# DVR8421.net
KiCad netlist of a schematic drawn in Altium Designer
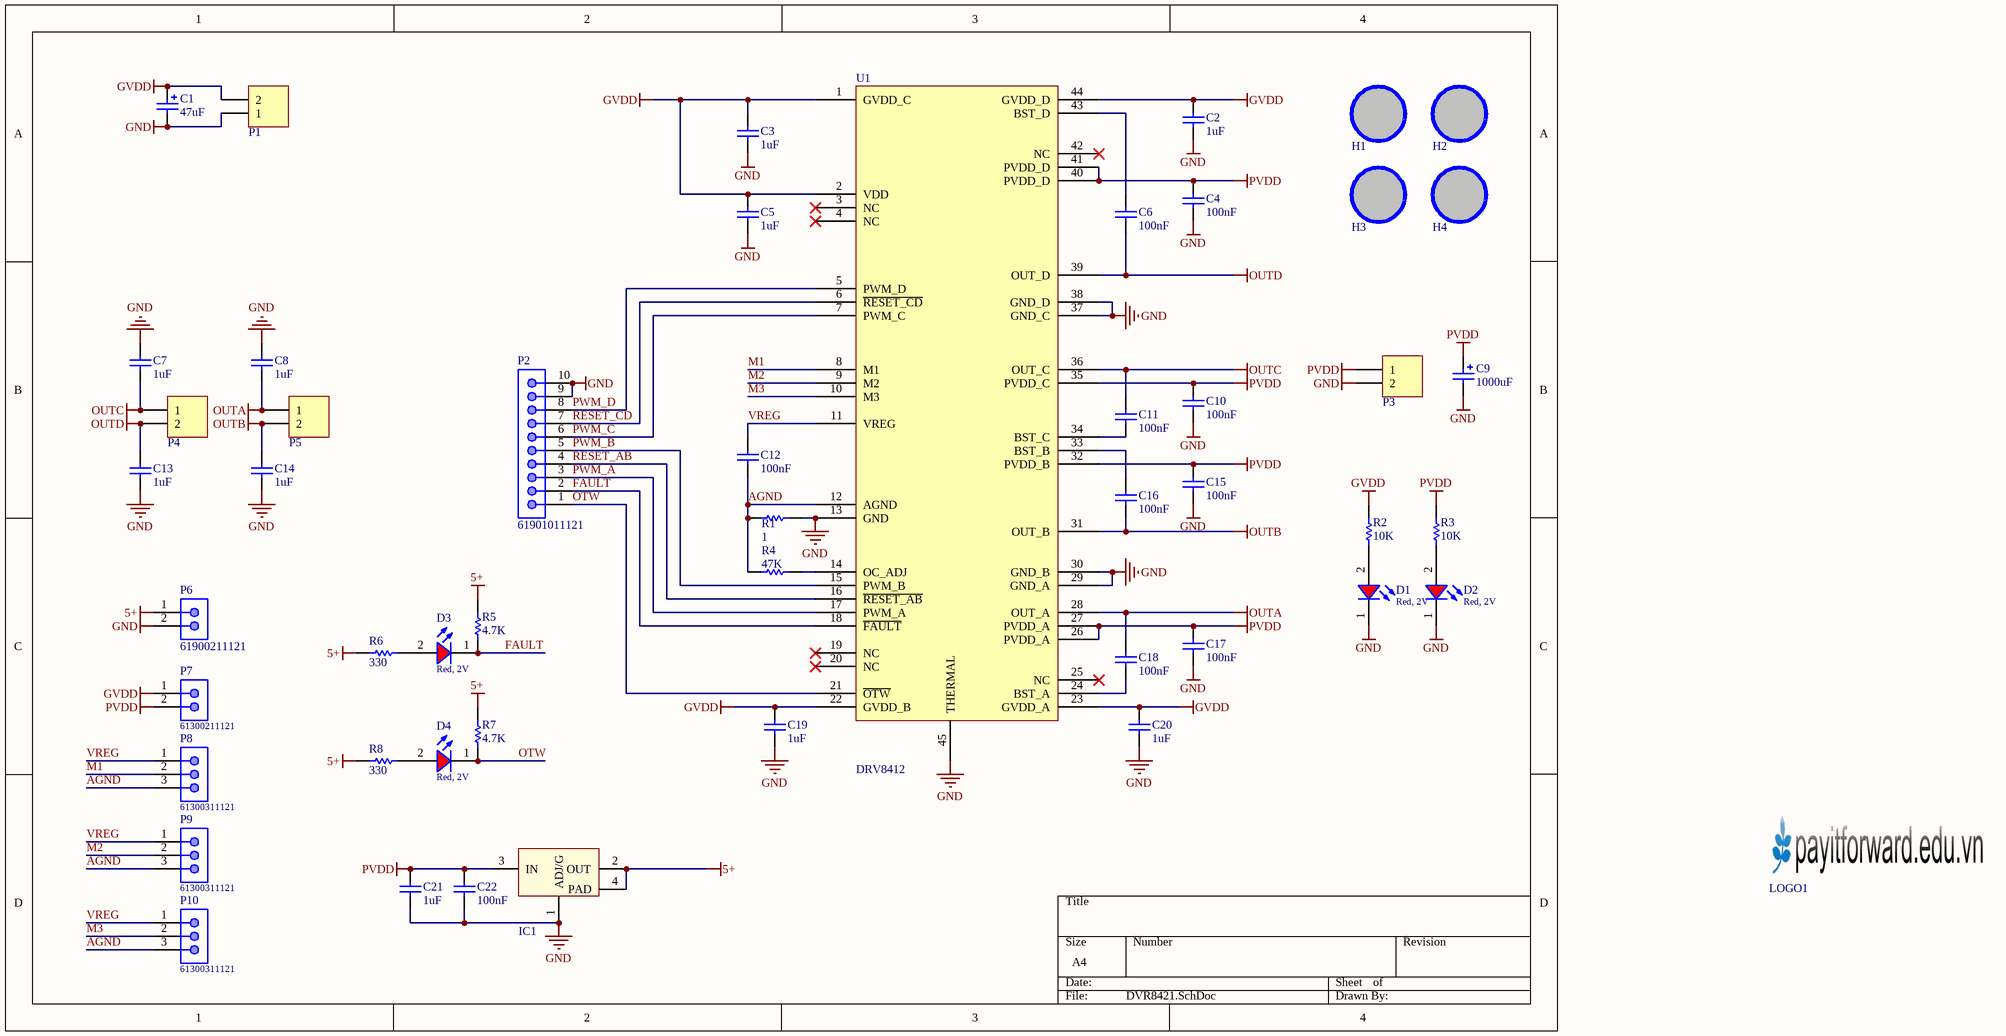
[diagram p0: DVR8421.SchDoc]

(export (version "E")
  (design (tool "Eeschema 10.0.6"))
  (components
    (comp (ref "C1")
      (value "47uF")
      (footprint "CAP ALU SIZE D")
      (description "Polarized Capacitor (Radial)")
      (fields (field (name "Comment") "Cap Pol SMD"))
      (libsource (lib "PIF_Library") (part "Cap Pol SMD"))
    )
    (comp (ref "C2")
      (value "1uF")
      (footprint "CAP-SM-0603")
      (description "Capacitor")
      (fields (field (name "Comment") "Cap Non-Pol SMD"))
      (libsource (lib "PIF_Library") (part "Cap Non-Pol SMD"))
    )
    (comp (ref "C3")
      (value "1uF")
      (footprint "CAP-SM-0603")
      (description "Capacitor")
      (fields (field (name "Comment") "Cap Non-Pol SMD"))
      (libsource (lib "PIF_Library") (part "Cap Non-Pol SMD"))
    )
    (comp (ref "C4")
      (value "100nF")
      (footprint "CAP-SM-0603")
      (description "Capacitor")
      (fields (field (name "Comment") "Cap Non-Pol SMD"))
      (libsource (lib "PIF_Library") (part "Cap Non-Pol SMD"))
    )
    (comp (ref "C5")
      (value "1uF")
      (footprint "CAP-SM-0603")
      (description "Capacitor")
      (fields (field (name "Comment") "Cap Non-Pol SMD"))
      (libsource (lib "PIF_Library") (part "Cap Non-Pol SMD"))
    )
    (comp (ref "C6")
      (value "100nF")
      (footprint "CAP-SM-0603")
      (description "Capacitor")
      (fields (field (name "Comment") "Cap Non-Pol SMD"))
      (libsource (lib "PIF_Library") (part "Cap Non-Pol SMD"))
    )
    (comp (ref "C7")
      (value "1uF")
      (footprint "CAP-SM-0805")
      (description "Capacitor")
      (fields (field (name "Comment") "Cap Non-Pol SMD"))
      (libsource (lib "PIF_Library") (part "Cap Non-Pol SMD"))
    )
    (comp (ref "C8")
      (value "1uF")
      (footprint "CAP-SM-0805")
      (description "Capacitor")
      (fields (field (name "Comment") "Cap Non-Pol SMD"))
      (libsource (lib "PIF_Library") (part "Cap Non-Pol SMD"))
    )
    (comp (ref "C9")
      (value "1000uF")
      (footprint "CP2/5")
      (description "Polarized Capacitor (Radial)")
      (fields (field (name "Comment") "Cap Pol"))
      (libsource (lib "PIF_Library") (part "Cap Pol"))
    )
    (comp (ref "C10")
      (value "100nF")
      (footprint "CAP-SM-0603")
      (description "Capacitor")
      (fields (field (name "Comment") "Cap Non-Pol SMD"))
      (libsource (lib "PIF_Library") (part "Cap Non-Pol SMD"))
    )
    (comp (ref "C11")
      (value "100nF")
      (footprint "CAP-SM-0603")
      (description "Capacitor")
      (fields (field (name "Comment") "Cap Non-Pol SMD"))
      (libsource (lib "PIF_Library") (part "Cap Non-Pol SMD"))
    )
    (comp (ref "C12")
      (value "100nF")
      (footprint "CAP-SM-0603")
      (description "Capacitor")
      (fields (field (name "Comment") "Cap Non-Pol SMD"))
      (libsource (lib "PIF_Library") (part "Cap Non-Pol SMD"))
    )
    (comp (ref "C13")
      (value "1uF")
      (footprint "CAP-SM-0805")
      (description "Capacitor")
      (fields (field (name "Comment") "Cap Non-Pol SMD"))
      (libsource (lib "PIF_Library") (part "Cap Non-Pol SMD"))
    )
    (comp (ref "C14")
      (value "1uF")
      (footprint "CAP-SM-0805")
      (description "Capacitor")
      (fields (field (name "Comment") "Cap Non-Pol SMD"))
      (libsource (lib "PIF_Library") (part "Cap Non-Pol SMD"))
    )
    (comp (ref "C15")
      (value "100nF")
      (footprint "CAP-SM-0603")
      (description "Capacitor")
      (fields (field (name "Comment") "Cap Non-Pol SMD"))
      (libsource (lib "PIF_Library") (part "Cap Non-Pol SMD"))
    )
    (comp (ref "C16")
      (value "100nF")
      (footprint "CAP-SM-0603")
      (description "Capacitor")
      (fields (field (name "Comment") "Cap Non-Pol SMD"))
      (libsource (lib "PIF_Library") (part "Cap Non-Pol SMD"))
    )
    (comp (ref "C17")
      (value "100nF")
      (footprint "CAP-SM-0603")
      (description "Capacitor")
      (fields (field (name "Comment") "Cap Non-Pol SMD"))
      (libsource (lib "PIF_Library") (part "Cap Non-Pol SMD"))
    )
    (comp (ref "C18")
      (value "100nF")
      (footprint "CAP-SM-0603")
      (description "Capacitor")
      (fields (field (name "Comment") "Cap Non-Pol SMD"))
      (libsource (lib "PIF_Library") (part "Cap Non-Pol SMD"))
    )
    (comp (ref "C19")
      (value "1uF")
      (footprint "CAP-SM-0603")
      (description "Capacitor")
      (fields (field (name "Comment") "Cap Non-Pol SMD"))
      (libsource (lib "PIF_Library") (part "Cap Non-Pol SMD"))
    )
    (comp (ref "C20")
      (value "1uF")
      (footprint "CAP-SM-0603")
      (description "Capacitor")
      (fields (field (name "Comment") "Cap Non-Pol SMD"))
      (libsource (lib "PIF_Library") (part "Cap Non-Pol SMD"))
    )
    (comp (ref "C21")
      (value "1uF")
      (footprint "CAP-SM-0603")
      (description "Capacitor")
      (fields (field (name "Comment") "Cap Non-Pol SMD"))
      (libsource (lib "PIF_Library") (part "Cap Non-Pol SMD"))
    )
    (comp (ref "C22")
      (value "100nF")
      (footprint "CAP-SM-0603")
      (description "Capacitor")
      (fields (field (name "Comment") "Cap Non-Pol SMD"))
      (libsource (lib "PIF_Library") (part "Cap Non-Pol SMD"))
    )
    (comp (ref "D1")
      (value "Red, 2V")
      (footprint "WL-SMCW_0603_H=0.7mm")
      (description "WL-SMCW SMT Mono-color Chip LED Waterclear, size 0603, Red, 2V, 140deg")
      (fields (field (name "PART NUMBER") "150060RS75000") (field (name "PUBLISHER") "Wurth Elektronik"))
      (libsource (lib "Altium_WL-SMCW (rev20a)") (part "150060RS75000"))
    )
    (comp (ref "D2")
      (value "Red, 2V")
      (footprint "WL-SMCW_0603_H=0.7mm")
      (description "WL-SMCW SMT Mono-color Chip LED Waterclear, size 0603, Red, 2V, 140deg")
      (fields (field (name "PART NUMBER") "150060RS75000") (field (name "PUBLISHER") "Wurth Elektronik"))
      (libsource (lib "Altium_WL-SMCW (rev20a)") (part "150060RS75000"))
    )
    (comp (ref "D3")
      (value "Red, 2V")
      (footprint "WL-SMCW_0603_H=0.7mm")
      (description "WL-SMCW SMT Mono-color Chip LED Waterclear, size 0603, Red, 2V, 140deg")
      (fields (field (name "PART NUMBER") "150060RS75000") (field (name "PUBLISHER") "Wurth Elektronik"))
      (libsource (lib "Altium_WL-SMCW (rev20a)") (part "150060RS75000"))
    )
    (comp (ref "D4")
      (value "Red, 2V")
      (footprint "WL-SMCW_0603_H=0.7mm")
      (description "WL-SMCW SMT Mono-color Chip LED Waterclear, size 0603, Red, 2V, 140deg")
      (fields (field (name "PART NUMBER") "150060RS75000") (field (name "PUBLISHER") "Wurth Elektronik"))
      (libsource (lib "Altium_WL-SMCW (rev20a)") (part "150060RS75000"))
    )
    (comp (ref "H1")
      (value "Hole")
      (footprint "LO KHOAN 3MM")
      (description "Hole 3mm")
      (libsource (lib "PIF_Library") (part "Hole"))
    )
    (comp (ref "H2")
      (value "Hole")
      (footprint "LO KHOAN 3MM")
      (description "Hole 3mm")
      (libsource (lib "PIF_Library") (part "Hole"))
    )
    (comp (ref "H3")
      (value "Hole")
      (footprint "LO KHOAN 3MM")
      (description "Hole 3mm")
      (libsource (lib "PIF_Library") (part "Hole"))
    )
    (comp (ref "H4")
      (value "Hole")
      (footprint "LO KHOAN 3MM")
      (description "Hole 3mm")
      (libsource (lib "PIF_Library") (part "Hole"))
    )
    (comp (ref "IC1")
      (value "LM1117")
      (footprint "SOT223-4N")
      (description "Available in 1.8V, 2.5V, 2.85V, 3.3V, 5V, and  Adjustable Versions")
      (libsource (lib "PIF_Library") (part "LM1117"))
    )
    (comp (ref "LOGO1")
      (value "LOGO PIF")
      (footprint "PIF LOGO SMALL TOP")
      (libsource (lib "PIF_Library") (part "LOGO PIF"))
    )
    (comp (ref "P1")
      (value "Domino 2")
      (footprint "DOMINO 2- 5mm")
      (description "Domino, 2-Pin")
      (fields (field (name "PUBLISHER") "Altium Limited"))
      (libsource (lib "") (part "Domino 2_1"))
    )
    (comp (ref "P2")
      (value "61901011121")
      (footprint "61901011121")
      (description "WR-WTB THT Male Vertical Locking Header, pitch 2.54mm, 10p")
      (fields (field (name "PUBLISHER") "Wurth Elektronik"))
      (libsource (lib "653008114822_Altium_WR-WTB_rev20a") (part "61901011121"))
    )
    (comp (ref "P3")
      (value "Domino 2")
      (footprint "DOMINO 2- 5mm")
      (description "Domino, 2-Pin")
      (fields (field (name "PUBLISHER") "Altium Limited"))
      (libsource (lib "PIF_Library") (part "Domino 2"))
    )
    (comp (ref "P4")
      (value "Domino 2")
      (footprint "DOMINO 2- 5mm")
      (description "Domino, 2-Pin")
      (fields (field (name "PUBLISHER") "Altium Limited"))
      (libsource (lib "PIF_Library") (part "Domino 2"))
    )
    (comp (ref "P5")
      (value "Domino 2")
      (footprint "DOMINO 2- 5mm")
      (description "Domino, 2-Pin")
      (fields (field (name "PUBLISHER") "Altium Limited"))
      (libsource (lib "PIF_Library") (part "Domino 2"))
    )
    (comp (ref "P6")
      (value "61900211121")
      (footprint "61900211121")
      (description "WR-WTB THT Male Vertical Locking Header, pitch 2.54mm, 2p")
      (fields (field (name "PUBLISHER") "Wurth Elektronik"))
      (libsource (lib "653008114822_Altium_WR-WTB_rev20a") (part "61900211121"))
    )
    (comp (ref "P7")
      (value "61300211121")
      (footprint "61300211121")
      (description "WR-PHD Pin Header, THT, pitch 2.54mm, Single Row, Vertical, 2p")
      (fields (field (name "MANUFACTURER") "Wurth Elektronik"))
      (libsource (lib "Altium_WR-PHD (rev20a)") (part "61300211121"))
    )
    (comp (ref "P8")
      (value "61300311121")
      (footprint "61300311121")
      (description "WR-PHD Pin Header, THT, pitch 2.54mm, Single Row, Vertical, 3p")
      (fields (field (name "MANUFACTURER") "Wurth Elektronik"))
      (libsource (lib "Altium_WR-PHD (rev20a)") (part "61300311121"))
    )
    (comp (ref "P9")
      (value "61300311121")
      (footprint "61300311121")
      (description "WR-PHD Pin Header, THT, pitch 2.54mm, Single Row, Vertical, 3p")
      (fields (field (name "MANUFACTURER") "Wurth Elektronik"))
      (libsource (lib "Altium_WR-PHD (rev20a)") (part "61300311121"))
    )
    (comp (ref "P10")
      (value "61300311121")
      (footprint "61300311121")
      (description "WR-PHD Pin Header, THT, pitch 2.54mm, Single Row, Vertical, 3p")
      (fields (field (name "MANUFACTURER") "Wurth Elektronik"))
      (libsource (lib "Altium_WR-PHD (rev20a)") (part "61300311121"))
    )
    (comp (ref "R1")
      (value "1")
      (footprint "RES-SM-0603")
      (description "Resistor")
      (fields (field (name "Comment") "RESISTOR SMD"))
      (libsource (lib "PIF_Library") (part "RESISTOR SMD"))
    )
    (comp (ref "R2")
      (value "10K")
      (footprint "RES-SM-0603")
      (description "Resistor")
      (fields (field (name "Comment") "RESISTOR SMD"))
      (libsource (lib "PIF_Library") (part "RESISTOR SMD"))
    )
    (comp (ref "R3")
      (value "10K")
      (footprint "RES-SM-0603")
      (description "Resistor")
      (fields (field (name "Comment") "RESISTOR SMD"))
      (libsource (lib "PIF_Library") (part "RESISTOR SMD"))
    )
    (comp (ref "R4")
      (value "47K")
      (footprint "RES-SM-0603")
      (description "Resistor")
      (fields (field (name "Comment") "RESISTOR SMD"))
      (libsource (lib "PIF_Library") (part "RESISTOR SMD"))
    )
    (comp (ref "R5")
      (value "4.7K")
      (footprint "RES-SM-0603")
      (description "Resistor")
      (fields (field (name "Comment") "RESISTOR SMD"))
      (libsource (lib "PIF_Library") (part "RESISTOR SMD"))
    )
    (comp (ref "R6")
      (value "330")
      (footprint "RES-SM-0603")
      (description "Resistor")
      (fields (field (name "Comment") "RESISTOR SMD"))
      (libsource (lib "PIF_Library") (part "RESISTOR SMD"))
    )
    (comp (ref "R7")
      (value "4.7K")
      (footprint "RES-SM-0603")
      (description "Resistor")
      (fields (field (name "Comment") "RESISTOR SMD"))
      (libsource (lib "PIF_Library") (part "RESISTOR SMD"))
    )
    (comp (ref "R8")
      (value "330")
      (footprint "RES-SM-0603")
      (description "Resistor")
      (fields (field (name "Comment") "RESISTOR SMD"))
      (libsource (lib "PIF_Library") (part "RESISTOR SMD"))
    )
    (comp (ref "U1")
      (value "DRV8412")
      (footprint "TSOP64P810X150_HS-45N")
      (fields (field (name "MANUFACTURER") "Texas Instruments"))
      (libsource (lib "MiclsLib") (part "DRV8412"))
    )
  )
  (nets
    (net (code "1") (name "/AGND") (class "Default")
      (node (ref "C12") (pin "1") (pinfunction "1_1") (pintype "passive"))
      (node (ref "P10") (pin "3") (pinfunction "3_3") (pintype "passive"))
      (node (ref "P8") (pin "3") (pinfunction "3_3") (pintype "passive"))
      (node (ref "P9") (pin "3") (pinfunction "3_3") (pintype "passive"))
      (node (ref "R1") (pin "1") (pinfunction "1_1") (pintype "passive"))
      (node (ref "R4") (pin "1") (pinfunction "1_1") (pintype "passive"))
      (node (ref "U1") (pin "12") (pinfunction "AGND_12") (pintype "passive"))
    )
    (net (code "2") (name "/FAULT") (class "Default")
      (node (ref "D3") (pin "1") (pinfunction "K_1") (pintype "passive"))
      (node (ref "P2") (pin "2") (pinfunction "2_2") (pintype "passive"))
      (node (ref "R5") (pin "1") (pinfunction "1_1") (pintype "passive"))
      (node (ref "U1") (pin "18") (pinfunction "~{FAULT}_18") (pintype "passive"))
    )
    (net (code "3") (name "/M1") (class "Default")
      (node (ref "P8") (pin "2") (pinfunction "2_2") (pintype "passive"))
      (node (ref "U1") (pin "8") (pinfunction "M1_8") (pintype "passive"))
    )
    (net (code "4") (name "/M2") (class "Default")
      (node (ref "P9") (pin "2") (pinfunction "2_2") (pintype "passive"))
      (node (ref "U1") (pin "9") (pinfunction "M2_9") (pintype "passive"))
    )
    (net (code "5") (name "/M3") (class "Default")
      (node (ref "P10") (pin "2") (pinfunction "2_2") (pintype "passive"))
      (node (ref "U1") (pin "10") (pinfunction "M3_10") (pintype "passive"))
    )
    (net (code "6") (name "/OTW") (class "Default")
      (node (ref "D4") (pin "1") (pinfunction "K_1") (pintype "passive"))
      (node (ref "P2") (pin "1") (pinfunction "1_1") (pintype "passive"))
      (node (ref "R7") (pin "1") (pinfunction "1_1") (pintype "passive"))
      (node (ref "U1") (pin "21") (pinfunction "~{OTW}_21") (pintype "passive"))
    )
    (net (code "7") (name "/PWM_A") (class "Default")
      (node (ref "P2") (pin "3") (pinfunction "3_3") (pintype "passive"))
      (node (ref "U1") (pin "17") (pinfunction "PWM_A_17") (pintype "passive"))
    )
    (net (code "8") (name "/PWM_B") (class "Default")
      (node (ref "P2") (pin "5") (pinfunction "5_5") (pintype "passive"))
      (node (ref "U1") (pin "15") (pinfunction "PWM_B_15") (pintype "passive"))
    )
    (net (code "9") (name "/PWM_C") (class "Default")
      (node (ref "P2") (pin "6") (pinfunction "6_6") (pintype "passive"))
      (node (ref "U1") (pin "7") (pinfunction "PWM_C_7") (pintype "passive"))
    )
    (net (code "10") (name "/PWM_D") (class "Default")
      (node (ref "P2") (pin "8") (pinfunction "8_8") (pintype "passive"))
      (node (ref "U1") (pin "5") (pinfunction "PWM_D_5") (pintype "passive"))
    )
    (net (code "11") (name "/RESET_AB") (class "Default")
      (node (ref "P2") (pin "4") (pinfunction "4_4") (pintype "passive"))
      (node (ref "U1") (pin "16") (pinfunction "~{RESET_AB}_16") (pintype "passive"))
    )
    (net (code "12") (name "/RESET_CD") (class "Default")
      (node (ref "P2") (pin "7") (pinfunction "7_7") (pintype "passive"))
      (node (ref "U1") (pin "6") (pinfunction "~{RESET_CD}_6") (pintype "passive"))
    )
    (net (code "13") (name "/VREG") (class "Default")
      (node (ref "C12") (pin "2") (pinfunction "2_2") (pintype "passive"))
      (node (ref "P10") (pin "1") (pinfunction "1_1") (pintype "passive"))
      (node (ref "P8") (pin "1") (pinfunction "1_1") (pintype "passive"))
      (node (ref "P9") (pin "1") (pinfunction "1_1") (pintype "passive"))
      (node (ref "U1") (pin "11") (pinfunction "VREG_11") (pintype "passive"))
    )
    (net (code "14") (name "5+") (class "Default")
      (node (ref "IC1") (pin "2") (pinfunction "OUT_2") (pintype "passive"))
      (node (ref "IC1") (pin "4") (pinfunction "PAD_4") (pintype "passive"))
      (node (ref "P6") (pin "1") (pinfunction "1_1") (pintype "passive"))
      (node (ref "R5") (pin "2") (pinfunction "2_2") (pintype "passive"))
      (node (ref "R6") (pin "2") (pinfunction "2_2") (pintype "passive"))
      (node (ref "R7") (pin "2") (pinfunction "2_2") (pintype "passive"))
      (node (ref "R8") (pin "2") (pinfunction "2_2") (pintype "passive"))
    )
    (net (code "15") (name "GND") (class "Default")
      (node (ref "C1") (pin "2") (pinfunction "2_2") (pintype "passive"))
      (node (ref "C10") (pin "1") (pinfunction "1_1") (pintype "passive"))
      (node (ref "C13") (pin "1") (pinfunction "1_1") (pintype "passive"))
      (node (ref "C14") (pin "1") (pinfunction "1_1") (pintype "passive"))
      (node (ref "C15") (pin "1") (pinfunction "1_1") (pintype "passive"))
      (node (ref "C17") (pin "1") (pinfunction "1_1") (pintype "passive"))
      (node (ref "C19") (pin "1") (pinfunction "1_1") (pintype "passive"))
      (node (ref "C2") (pin "1") (pinfunction "1_1") (pintype "passive"))
      (node (ref "C20") (pin "1") (pinfunction "1_1") (pintype "passive"))
      (node (ref "C21") (pin "1") (pinfunction "1_1") (pintype "passive"))
      (node (ref "C22") (pin "1") (pinfunction "1_1") (pintype "passive"))
      (node (ref "C3") (pin "1") (pinfunction "1_1") (pintype "passive"))
      (node (ref "C4") (pin "1") (pinfunction "1_1") (pintype "passive"))
      (node (ref "C5") (pin "1") (pinfunction "1_1") (pintype "passive"))
      (node (ref "C7") (pin "2") (pinfunction "2_2") (pintype "passive"))
      (node (ref "C8") (pin "2") (pinfunction "2_2") (pintype "passive"))
      (node (ref "C9") (pin "2") (pinfunction "2_2") (pintype "passive"))
      (node (ref "D1") (pin "1") (pinfunction "K_1") (pintype "passive"))
      (node (ref "D2") (pin "1") (pinfunction "K_1") (pintype "passive"))
      (node (ref "IC1") (pin "1") (pinfunction "ADJ/G_1") (pintype "passive"))
      (node (ref "P1") (pin "1") (pinfunction "1_1") (pintype "passive"))
      (node (ref "P2") (pin "10") (pinfunction "10_10") (pintype "passive"))
      (node (ref "P2") (pin "9") (pinfunction "9_9") (pintype "passive"))
      (node (ref "P3") (pin "2") (pinfunction "2_2") (pintype "passive"))
      (node (ref "P6") (pin "2") (pinfunction "2_2") (pintype "passive"))
      (node (ref "R1") (pin "2") (pinfunction "2_2") (pintype "passive"))
      (node (ref "U1") (pin "13") (pinfunction "GND_13") (pintype "passive"))
      (node (ref "U1") (pin "29") (pinfunction "GND_A_29") (pintype "passive"))
      (node (ref "U1") (pin "30") (pinfunction "GND_B_30") (pintype "passive"))
      (node (ref "U1") (pin "37") (pinfunction "GND_C_37") (pintype "passive"))
      (node (ref "U1") (pin "38") (pinfunction "GND_D_38") (pintype "passive"))
      (node (ref "U1") (pin "45") (pinfunction "THERMAL_45") (pintype "passive"))
    )
    (net (code "16") (name "GVDD") (class "Default")
      (node (ref "C1") (pin "1") (pinfunction "1_1") (pintype "passive"))
      (node (ref "C19") (pin "2") (pinfunction "2_2") (pintype "passive"))
      (node (ref "C2") (pin "2") (pinfunction "2_2") (pintype "passive"))
      (node (ref "C20") (pin "2") (pinfunction "2_2") (pintype "passive"))
      (node (ref "C3") (pin "2") (pinfunction "2_2") (pintype "passive"))
      (node (ref "C5") (pin "2") (pinfunction "2_2") (pintype "passive"))
      (node (ref "P1") (pin "2") (pinfunction "2_2") (pintype "passive"))
      (node (ref "P7") (pin "1") (pinfunction "1_1") (pintype "passive"))
      (node (ref "R2") (pin "1") (pinfunction "1_1") (pintype "passive"))
      (node (ref "U1") (pin "1") (pinfunction "GVDD_C_1") (pintype "passive"))
      (node (ref "U1") (pin "2") (pinfunction "VDD_2") (pintype "passive"))
      (node (ref "U1") (pin "22") (pinfunction "GVDD_B_22") (pintype "passive"))
      (node (ref "U1") (pin "23") (pinfunction "GVDD_A_23") (pintype "passive"))
      (node (ref "U1") (pin "44") (pinfunction "GVDD_D_44") (pintype "passive"))
    )
    (net (code "17") (name "Net-(D1-A)") (class "Default")
      (node (ref "D1") (pin "2") (pinfunction "A_2") (pintype "passive"))
      (node (ref "R2") (pin "2") (pinfunction "2_2") (pintype "passive"))
    )
    (net (code "18") (name "Net-(D2-A)") (class "Default")
      (node (ref "D2") (pin "2") (pinfunction "A_2") (pintype "passive"))
      (node (ref "R3") (pin "2") (pinfunction "2_2") (pintype "passive"))
    )
    (net (code "19") (name "Net-(D3-A)") (class "Default")
      (node (ref "D3") (pin "2") (pinfunction "A_2") (pintype "passive"))
      (node (ref "R6") (pin "1") (pinfunction "1_1") (pintype "passive"))
    )
    (net (code "20") (name "Net-(D4-A)") (class "Default")
      (node (ref "D4") (pin "2") (pinfunction "A_2") (pintype "passive"))
      (node (ref "R8") (pin "1") (pinfunction "1_1") (pintype "passive"))
    )
    (net (code "21") (name "Net-(U1-BST_A)") (class "Default")
      (node (ref "C18") (pin "1") (pinfunction "1_1") (pintype "passive"))
      (node (ref "U1") (pin "24") (pinfunction "BST_A_24") (pintype "passive"))
    )
    (net (code "22") (name "Net-(U1-BST_B)") (class "Default")
      (node (ref "C16") (pin "2") (pinfunction "2_2") (pintype "passive"))
      (node (ref "U1") (pin "33") (pinfunction "BST_B_33") (pintype "passive"))
    )
    (net (code "23") (name "Net-(U1-BST_C)") (class "Default")
      (node (ref "C11") (pin "1") (pinfunction "1_1") (pintype "passive"))
      (node (ref "U1") (pin "34") (pinfunction "BST_C_34") (pintype "passive"))
    )
    (net (code "24") (name "Net-(U1-BST_D)") (class "Default")
      (node (ref "C6") (pin "2") (pinfunction "2_2") (pintype "passive"))
      (node (ref "U1") (pin "43") (pinfunction "BST_D_43") (pintype "passive"))
    )
    (net (code "25") (name "Net-(U1-OC_ADJ)") (class "Default")
      (node (ref "R4") (pin "2") (pinfunction "2_2") (pintype "passive"))
      (node (ref "U1") (pin "14") (pinfunction "OC_ADJ_14") (pintype "passive"))
    )
    (net (code "26") (name "OUTA") (class "Default")
      (node (ref "C18") (pin "2") (pinfunction "2_2") (pintype "passive"))
      (node (ref "C8") (pin "1") (pinfunction "1_1") (pintype "passive"))
      (node (ref "P5") (pin "1") (pinfunction "1_1") (pintype "passive"))
      (node (ref "U1") (pin "28") (pinfunction "OUT_A_28") (pintype "passive"))
    )
    (net (code "27") (name "OUTB") (class "Default")
      (node (ref "C14") (pin "2") (pinfunction "2_2") (pintype "passive"))
      (node (ref "C16") (pin "1") (pinfunction "1_1") (pintype "passive"))
      (node (ref "P5") (pin "2") (pinfunction "2_2") (pintype "passive"))
      (node (ref "U1") (pin "31") (pinfunction "OUT_B_31") (pintype "passive"))
    )
    (net (code "28") (name "OUTC") (class "Default")
      (node (ref "C11") (pin "2") (pinfunction "2_2") (pintype "passive"))
      (node (ref "C7") (pin "1") (pinfunction "1_1") (pintype "passive"))
      (node (ref "P4") (pin "1") (pinfunction "1_1") (pintype "passive"))
      (node (ref "U1") (pin "36") (pinfunction "OUT_C_36") (pintype "passive"))
    )
    (net (code "29") (name "OUTD") (class "Default")
      (node (ref "C13") (pin "2") (pinfunction "2_2") (pintype "passive"))
      (node (ref "C6") (pin "1") (pinfunction "1_1") (pintype "passive"))
      (node (ref "P4") (pin "2") (pinfunction "2_2") (pintype "passive"))
      (node (ref "U1") (pin "39") (pinfunction "OUT_D_39") (pintype "passive"))
    )
    (net (code "30") (name "PVDD") (class "Default")
      (node (ref "C10") (pin "2") (pinfunction "2_2") (pintype "passive"))
      (node (ref "C15") (pin "2") (pinfunction "2_2") (pintype "passive"))
      (node (ref "C17") (pin "2") (pinfunction "2_2") (pintype "passive"))
      (node (ref "C21") (pin "2") (pinfunction "2_2") (pintype "passive"))
      (node (ref "C22") (pin "2") (pinfunction "2_2") (pintype "passive"))
      (node (ref "C4") (pin "2") (pinfunction "2_2") (pintype "passive"))
      (node (ref "C9") (pin "1") (pinfunction "1_1") (pintype "passive"))
      (node (ref "IC1") (pin "3") (pinfunction "IN_3") (pintype "passive"))
      (node (ref "P3") (pin "1") (pinfunction "1_1") (pintype "passive"))
      (node (ref "P7") (pin "2") (pinfunction "2_2") (pintype "passive"))
      (node (ref "R3") (pin "1") (pinfunction "1_1") (pintype "passive"))
      (node (ref "U1") (pin "26") (pinfunction "PVDD_A_26") (pintype "passive"))
      (node (ref "U1") (pin "27") (pinfunction "PVDD_A_27") (pintype "passive"))
      (node (ref "U1") (pin "32") (pinfunction "PVDD_B_32") (pintype "passive"))
      (node (ref "U1") (pin "35") (pinfunction "PVDD_C_35") (pintype "passive"))
      (node (ref "U1") (pin "40") (pinfunction "PVDD_D_40") (pintype "passive"))
      (node (ref "U1") (pin "41") (pinfunction "PVDD_D_41") (pintype "passive"))
    )
    (net (code "31") (name "unconnected-(H1-Pad1)") (class "Default")
      (node (ref "H1") (pin "1") (pinfunction "1_1") (pintype "passive"))
    )
    (net (code "32") (name "unconnected-(H2-Pad1)") (class "Default")
      (node (ref "H2") (pin "1") (pinfunction "1_1") (pintype "passive"))
    )
    (net (code "33") (name "unconnected-(H3-Pad1)") (class "Default")
      (node (ref "H3") (pin "1") (pinfunction "1_1") (pintype "passive"))
    )
    (net (code "34") (name "unconnected-(H4-Pad1)") (class "Default")
      (node (ref "H4") (pin "1") (pinfunction "1_1") (pintype "passive"))
    )
    (net (code "35") (name "unconnected-(U1-NC-Pad3)") (class "Default")
      (node (ref "U1") (pin "3") (pinfunction "NC_3") (pintype "passive+no_connect"))
    )
    (net (code "36") (name "unconnected-(U1-NC-Pad4)") (class "Default")
      (node (ref "U1") (pin "4") (pinfunction "NC_4") (pintype "passive+no_connect"))
    )
    (net (code "37") (name "unconnected-(U1-NC-Pad19)") (class "Default")
      (node (ref "U1") (pin "19") (pinfunction "NC_19") (pintype "passive+no_connect"))
    )
    (net (code "38") (name "unconnected-(U1-NC-Pad20)") (class "Default")
      (node (ref "U1") (pin "20") (pinfunction "NC_20") (pintype "passive+no_connect"))
    )
    (net (code "39") (name "unconnected-(U1-NC-Pad25)") (class "Default")
      (node (ref "U1") (pin "25") (pinfunction "NC_25") (pintype "passive+no_connect"))
    )
    (net (code "40") (name "unconnected-(U1-NC-Pad42)") (class "Default")
      (node (ref "U1") (pin "42") (pinfunction "NC_42") (pintype "passive+no_connect"))
    )
  )
)
